# TH3.net
KiCad netlist of a schematic drawn in Altium Designer
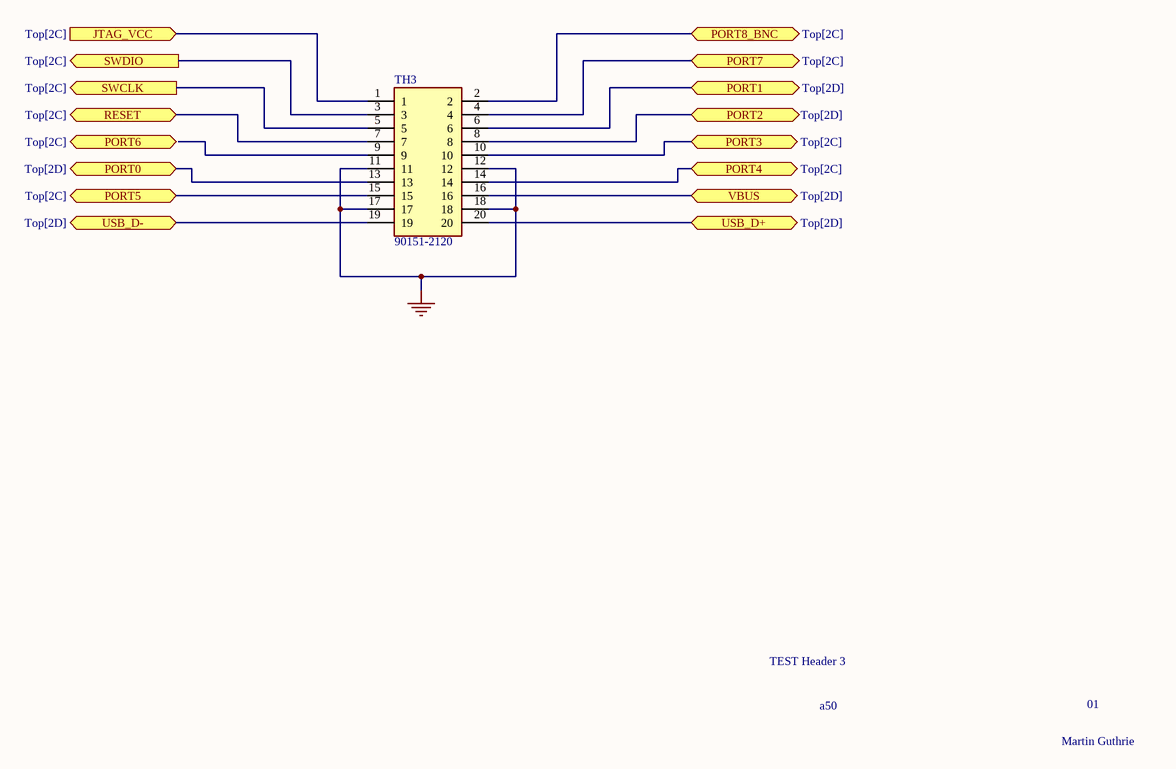
[diagram p0: TH3.SchDoc]

(export (version "E")
  (design (tool "Eeschema 10.0.6"))
  (components
    (comp (ref "TH3")
      (value "90151-2120")
      (footprint "PcbLib:90151-2120")
      (description "Connector")
      (fields (field (name "MOUSER PART NUMBER") "538-90151-2120"))
      (libsource (lib "SchematicLib") (part "90151-2120"))
    )
  )
  (nets
    (net (code "1") (name "/JTAG_VCC") (class "Default")
      (node (ref "TH3") (pin "1") (pinfunction "1_1") (pintype "passive"))
    )
    (net (code "2") (name "/PORT0") (class "Default")
      (node (ref "TH3") (pin "13") (pinfunction "13_13") (pintype "passive"))
    )
    (net (code "3") (name "/PORT1") (class "Default")
      (node (ref "TH3") (pin "6") (pinfunction "6_6") (pintype "passive"))
    )
    (net (code "4") (name "/PORT2") (class "Default")
      (node (ref "TH3") (pin "8") (pinfunction "8_8") (pintype "passive"))
    )
    (net (code "5") (name "/PORT3") (class "Default")
      (node (ref "TH3") (pin "10") (pinfunction "10_10") (pintype "passive"))
    )
    (net (code "6") (name "/PORT4") (class "Default")
      (node (ref "TH3") (pin "14") (pinfunction "14_14") (pintype "passive"))
    )
    (net (code "7") (name "/PORT5") (class "Default")
      (node (ref "TH3") (pin "15") (pinfunction "15_15") (pintype "passive"))
    )
    (net (code "9") (name "/PORT7") (class "Default")
      (node (ref "TH3") (pin "4") (pinfunction "4_4") (pintype "passive"))
    )
    (net (code "10") (name "/PORT8_BNC") (class "Default")
      (node (ref "TH3") (pin "2") (pinfunction "2_2") (pintype "passive"))
    )
    (net (code "11") (name "/RESET") (class "Default")
      (node (ref "TH3") (pin "7") (pinfunction "7_7") (pintype "passive"))
    )
    (net (code "12") (name "/SWCLK") (class "Default")
      (node (ref "TH3") (pin "5") (pinfunction "5_5") (pintype "passive"))
    )
    (net (code "13") (name "/SWDIO") (class "Default")
      (node (ref "TH3") (pin "3") (pinfunction "3_3") (pintype "passive"))
    )
    (net (code "14") (name "/USB_D+") (class "Default")
      (node (ref "TH3") (pin "20") (pinfunction "20_20") (pintype "passive"))
    )
    (net (code "15") (name "/USB_D-") (class "Default")
      (node (ref "TH3") (pin "19") (pinfunction "19_19") (pintype "passive"))
    )
    (net (code "16") (name "/VBUS") (class "Default")
      (node (ref "TH3") (pin "16") (pinfunction "16_16") (pintype "passive"))
    )
    (net (code "17") (name "GND") (class "Default")
      (node (ref "TH3") (pin "11") (pinfunction "11_11") (pintype "passive"))
      (node (ref "TH3") (pin "12") (pinfunction "12_12") (pintype "passive"))
      (node (ref "TH3") (pin "17") (pinfunction "17_17") (pintype "passive"))
      (node (ref "TH3") (pin "18") (pinfunction "18_18") (pintype "passive"))
    )
    (net (code "18") (name "unconnected-(TH3-Pad9)") (class "Default")
      (node (ref "TH3") (pin "9") (pinfunction "9_9") (pintype "passive"))
    )
  )
)
